# Power_1.net
KiCad netlist of a schematic drawn in Altium Designer
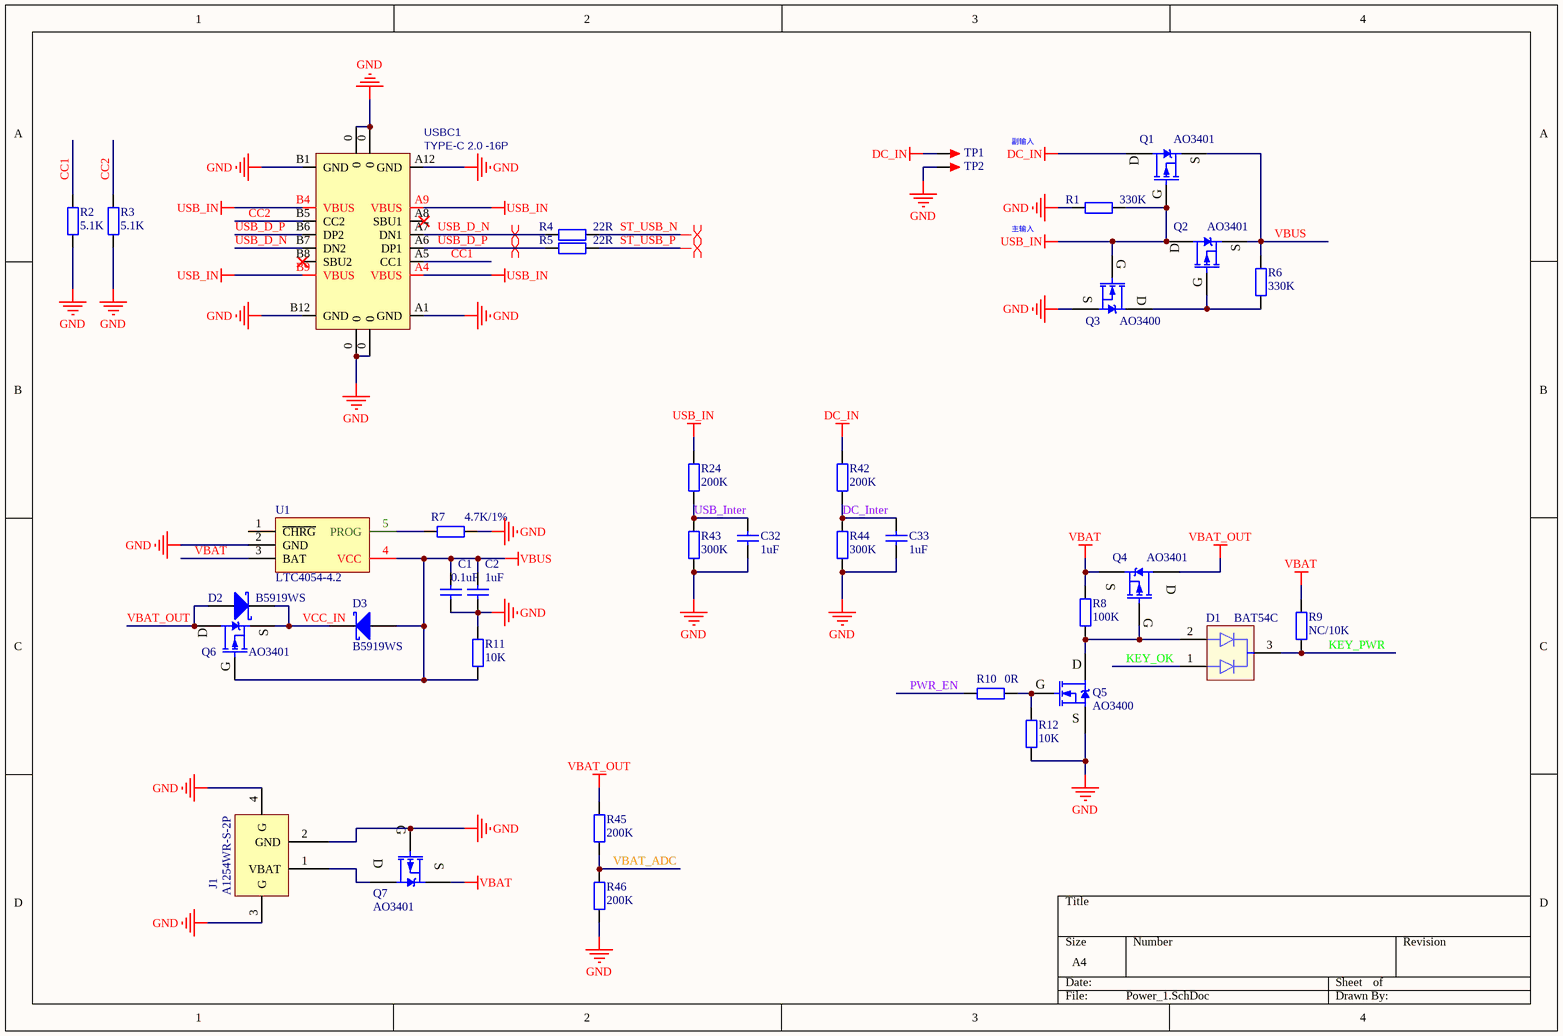
[diagram p0: Power_1.SchDoc]

(export (version "E")
  (design (tool "Eeschema 10.0.6"))
  (components
    (comp (ref "C1")
      (value "0.1uF")
      (footprint "C0402_L")
      (description "贴片电容")
      (libsource (lib "0.1 - 电阻-电容-电感-晶振-晶体-磁珠-电位器") (part "C"))
    )
    (comp (ref "C2")
      (value "1uF")
      (footprint "C0402_L")
      (description "贴片电容")
      (libsource (lib "0.1 - 电阻-电容-电感-晶振-晶体-磁珠-电位器") (part "C"))
    )
    (comp (ref "C32")
      (value "1uF")
      (footprint "C0402_L")
      (description "贴片电容")
      (libsource (lib "0.1 - 电阻-电容-电感-晶振-晶体-磁珠-电位器") (part "C"))
    )
    (comp (ref "C33")
      (value "1uF")
      (footprint "C0402_L")
      (description "贴片电容")
      (libsource (lib "0.1 - 电阻-电容-电感-晶振-晶体-磁珠-电位器") (part "C"))
    )
    (comp (ref "D1")
      (value "BAT54C")
      (footprint "SOT23-3L")
      (description "共阴肖特基二极管")
      (libsource (lib "USER_Lib") (part "BAT54C"))
    )
    (comp (ref "D2")
      (value "B5919WS")
      (footprint "SOD-123F")
      (description "肖特基二极管")
      (libsource (lib "0.2 - 二极管-TVS-ESD-整流桥") (part "1N5819"))
    )
    (comp (ref "D3")
      (value "B5919WS")
      (footprint "SOD-123F")
      (description "肖特基二极管")
      (libsource (lib "0.2 - 二极管-TVS-ESD-整流桥") (part "1N5819"))
    )
    (comp (ref "J1")
      (value "A1254WR-S-2P")
      (footprint "A1254WR-S-2P")
      (description "长江连接器-卧式-2P")
      (libsource (lib "USER_Lib") (part "A1254WR-S-2P"))
    )
    (comp (ref "Q1")
      (value "AO3401")
      (footprint "SOT23-3L")
      (description "P沟道 30V/4.2A")
      (libsource (lib "0.4 - 三极管-场效应管-可控硅") (part "AO3401"))
    )
    (comp (ref "Q2")
      (value "AO3401")
      (footprint "SOT23-3L")
      (description "P沟道 30V/4.2A")
      (libsource (lib "0.4 - 三极管-场效应管-可控硅") (part "AO3401"))
    )
    (comp (ref "Q3")
      (value "AO3400")
      (footprint "SOT23-3L")
      (description "N沟道 30V/4.2A")
      (libsource (lib "0.4 - 三极管-场效应管-可控硅") (part "AO3400"))
    )
    (comp (ref "Q4")
      (value "AO3401")
      (footprint "SOT23-3L")
      (description "P沟道 30V/4.2A")
      (libsource (lib "0.4 - 三极管-场效应管-可控硅") (part "AO3401"))
    )
    (comp (ref "Q5")
      (value "AO3400")
      (footprint "SOT23-3L")
      (description "N沟道 30V/4.2A")
      (libsource (lib "0.4 - 三极管-场效应管-可控硅") (part "AO3400"))
    )
    (comp (ref "Q6")
      (value "AO3401")
      (footprint "SOT23-3L")
      (description "P沟道 30V/4.2A")
      (libsource (lib "0.4 - 三极管-场效应管-可控硅") (part "AO3401"))
    )
    (comp (ref "Q7")
      (value "AO3401")
      (footprint "SOT23-3L")
      (description "P沟道 30V/4.2A")
      (libsource (lib "0.4 - 三极管-场效应管-可控硅") (part "AO3401"))
    )
    (comp (ref "R1")
      (value "330K")
      (footprint "R0402_L")
      (description "贴片电阻")
      (libsource (lib "0.1 - 电阻-电容-电感-晶振-晶体-磁珠-电位器") (part "R"))
    )
    (comp (ref "R2")
      (value "5.1K")
      (footprint "R0402_L")
      (description "贴片电阻")
      (libsource (lib "0.1 - 电阻-电容-电感-晶振-晶体-磁珠-电位器") (part "R"))
    )
    (comp (ref "R3")
      (value "5.1K")
      (footprint "R0402_L")
      (description "贴片电阻")
      (libsource (lib "0.1 - 电阻-电容-电感-晶振-晶体-磁珠-电位器") (part "R"))
    )
    (comp (ref "R4")
      (value "22R")
      (footprint "R0402_L")
      (description "贴片电阻")
      (libsource (lib "0.1 - 电阻-电容-电感-晶振-晶体-磁珠-电位器") (part "R"))
    )
    (comp (ref "R5")
      (value "22R")
      (footprint "R0402_L")
      (description "贴片电阻")
      (libsource (lib "0.1 - 电阻-电容-电感-晶振-晶体-磁珠-电位器") (part "R"))
    )
    (comp (ref "R6")
      (value "330K")
      (footprint "R0402_L")
      (description "贴片电阻")
      (libsource (lib "0.1 - 电阻-电容-电感-晶振-晶体-磁珠-电位器") (part "R"))
    )
    (comp (ref "R7")
      (value "4.7K/1%")
      (footprint "R0402_L")
      (description "贴片电阻")
      (libsource (lib "0.1 - 电阻-电容-电感-晶振-晶体-磁珠-电位器") (part "R"))
    )
    (comp (ref "R8")
      (value "100K")
      (footprint "R0402_L")
      (description "贴片电阻")
      (libsource (lib "0.1 - 电阻-电容-电感-晶振-晶体-磁珠-电位器") (part "R"))
    )
    (comp (ref "R9")
      (value "NC/10K")
      (footprint "R0402_L")
      (description "贴片电阻")
      (libsource (lib "0.1 - 电阻-电容-电感-晶振-晶体-磁珠-电位器") (part "R"))
    )
    (comp (ref "R10")
      (value "0R")
      (footprint "R0402_L")
      (description "贴片电阻")
      (libsource (lib "0.1 - 电阻-电容-电感-晶振-晶体-磁珠-电位器") (part "R"))
    )
    (comp (ref "R11")
      (value "10K")
      (footprint "R0402_L")
      (description "贴片电阻")
      (libsource (lib "0.1 - 电阻-电容-电感-晶振-晶体-磁珠-电位器") (part "R"))
    )
    (comp (ref "R12")
      (value "10K")
      (footprint "R0402_L")
      (description "贴片电阻")
      (libsource (lib "0.1 - 电阻-电容-电感-晶振-晶体-磁珠-电位器") (part "R"))
    )
    (comp (ref "R24")
      (value "200K")
      (footprint "R0402_L")
      (description "贴片电阻")
      (libsource (lib "0.1 - 电阻-电容-电感-晶振-晶体-磁珠-电位器") (part "R"))
    )
    (comp (ref "R42")
      (value "200K")
      (footprint "R0402_L")
      (description "贴片电阻")
      (libsource (lib "0.1 - 电阻-电容-电感-晶振-晶体-磁珠-电位器") (part "R"))
    )
    (comp (ref "R43")
      (value "300K")
      (footprint "R0402_L")
      (description "贴片电阻")
      (libsource (lib "0.1 - 电阻-电容-电感-晶振-晶体-磁珠-电位器") (part "R"))
    )
    (comp (ref "R44")
      (value "300K")
      (footprint "R0402_L")
      (description "贴片电阻")
      (libsource (lib "0.1 - 电阻-电容-电感-晶振-晶体-磁珠-电位器") (part "R"))
    )
    (comp (ref "R45")
      (value "200K")
      (footprint "R0402_L")
      (description "贴片电阻")
      (libsource (lib "0.1 - 电阻-电容-电感-晶振-晶体-磁珠-电位器") (part "R"))
    )
    (comp (ref "R46")
      (value "200K")
      (footprint "R0402_L")
      (description "贴片电阻")
      (libsource (lib "0.1 - 电阻-电容-电感-晶振-晶体-磁珠-电位器") (part "R"))
    )
    (comp (ref "TP1")
      (value "TEST")
      (footprint "TEST 1")
      (description "测试点")
      (libsource (lib "0.5 - 按键-开关-蜂鸣器-保险丝-电池-测试点-Mark点") (part "TEST"))
    )
    (comp (ref "TP2")
      (value "TEST")
      (footprint "TEST 1")
      (description "测试点")
      (libsource (lib "0.5 - 按键-开关-蜂鸣器-保险丝-电池-测试点-Mark点") (part "TEST"))
    )
    (comp (ref "U1")
      (value "LTC4054-4.2")
      (footprint "SOT23-5L")
      (description "锂电池充电IC")
      (libsource (lib "USER_Lib") (part "LTC4054-4.2"))
    )
    (comp (ref "USBC1")
      (value "TYPE-C 2.0 -16P")
      (footprint "USB-C-SMD_16P")
      (description "USB2.0_Type-C_16Pin母座")
      (libsource (lib "0.6 - 电源-以太网-音频-Type-C USB插座") (part "USB2.0_Type-C_16Pin"))
    )
  )
  (nets
    (net (code "1") (name "/CC1") (class "Default")
      (node (ref "R2") (pin "2") (pinfunction "2_2") (pintype "passive"))
      (node (ref "USBC1") (pin "A5") (pinfunction "CC1_A5") (pintype "passive"))
    )
    (net (code "2") (name "/CC2") (class "Default")
      (node (ref "R3") (pin "2") (pinfunction "2_2") (pintype "passive"))
      (node (ref "USBC1") (pin "B5") (pinfunction "CC2_B5") (pintype "passive"))
    )
    (net (code "3") (name "/DC_Inter") (class "Default")
      (node (ref "C33") (pin "2") (pinfunction "2_2") (pintype "passive"))
      (node (ref "R42") (pin "1") (pinfunction "1_1") (pintype "passive"))
      (node (ref "R44") (pin "2") (pinfunction "2_2") (pintype "passive"))
    )
    (net (code "4") (name "/KEY_OK") (class "Default")
      (node (ref "D1") (pin "1") (pinfunction "1_1") (pintype "passive"))
    )
    (net (code "5") (name "/KEY_PWR") (class "Default")
      (node (ref "D1") (pin "3") (pinfunction "3_3") (pintype "passive"))
      (node (ref "R9") (pin "1") (pinfunction "1_1") (pintype "passive"))
    )
    (net (code "6") (name "/PWR_EN") (class "Default")
      (node (ref "R10") (pin "2") (pinfunction "2_2") (pintype "passive"))
    )
    (net (code "7") (name "/ST_USB_N") (class "Default")
      (node (ref "R4") (pin "2") (pinfunction "2_2") (pintype "passive"))
    )
    (net (code "8") (name "/ST_USB_P") (class "Default")
      (node (ref "R5") (pin "2") (pinfunction "2_2") (pintype "passive"))
    )
    (net (code "9") (name "/USB_D_N") (class "Default")
      (node (ref "R4") (pin "1") (pinfunction "1_1") (pintype "passive"))
      (node (ref "USBC1") (pin "A7") (pinfunction "DN1_A7") (pintype "passive"))
      (node (ref "USBC1") (pin "B7") (pinfunction "DN2_B7") (pintype "passive"))
    )
    (net (code "10") (name "/USB_D_P") (class "Default")
      (node (ref "R5") (pin "1") (pinfunction "1_1") (pintype "passive"))
      (node (ref "USBC1") (pin "A6") (pinfunction "DP1_A6") (pintype "passive"))
      (node (ref "USBC1") (pin "B6") (pinfunction "DP2_B6") (pintype "passive"))
    )
    (net (code "11") (name "/USB_Inter") (class "Default")
      (node (ref "C32") (pin "2") (pinfunction "2_2") (pintype "passive"))
      (node (ref "R24") (pin "1") (pinfunction "1_1") (pintype "passive"))
      (node (ref "R43") (pin "2") (pinfunction "2_2") (pintype "passive"))
    )
    (net (code "12") (name "/VBAT_ADC") (class "Default")
      (node (ref "R45") (pin "1") (pinfunction "1_1") (pintype "passive"))
      (node (ref "R46") (pin "2") (pinfunction "2_2") (pintype "passive"))
    )
    (net (code "13") (name "/VCC_IN") (class "Default")
      (node (ref "D2") (pin "2") (pinfunction "K_2") (pintype "passive"))
      (node (ref "D3") (pin "2") (pinfunction "K_2") (pintype "passive"))
      (node (ref "Q6") (pin "2") (pinfunction "S_2") (pintype "passive"))
    )
    (net (code "14") (name "DC_IN") (class "Default")
      (node (ref "Q1") (pin "3") (pinfunction "D_3") (pintype "passive"))
      (node (ref "R42") (pin "2") (pinfunction "2_2") (pintype "passive"))
      (node (ref "TP1") (pin "1") (pinfunction "1_1") (pintype "passive"))
    )
    (net (code "15") (name "GND") (class "Default")
      (node (ref "C1") (pin "2") (pinfunction "2_2") (pintype "passive"))
      (node (ref "C2") (pin "2") (pinfunction "2_2") (pintype "passive"))
      (node (ref "C32") (pin "1") (pinfunction "1_1") (pintype "passive"))
      (node (ref "C33") (pin "1") (pinfunction "1_1") (pintype "passive"))
      (node (ref "J1") (pin "2") (pinfunction "GND_2") (pintype "passive"))
      (node (ref "J1") (pin "3") (pinfunction "G_3") (pintype "passive"))
      (node (ref "J1") (pin "4") (pinfunction "G_4") (pintype "passive"))
      (node (ref "Q3") (pin "2") (pinfunction "S_2") (pintype "passive"))
      (node (ref "Q5") (pin "2") (pinfunction "S_2") (pintype "passive"))
      (node (ref "Q7") (pin "1") (pinfunction "G_1") (pintype "passive"))
      (node (ref "R1") (pin "1") (pinfunction "1_1") (pintype "passive"))
      (node (ref "R11") (pin "2") (pinfunction "2_2") (pintype "passive"))
      (node (ref "R12") (pin "2") (pinfunction "2_2") (pintype "passive"))
      (node (ref "R2") (pin "1") (pinfunction "1_1") (pintype "passive"))
      (node (ref "R3") (pin "1") (pinfunction "1_1") (pintype "passive"))
      (node (ref "R43") (pin "1") (pinfunction "1_1") (pintype "passive"))
      (node (ref "R44") (pin "1") (pinfunction "1_1") (pintype "passive"))
      (node (ref "R46") (pin "1") (pinfunction "1_1") (pintype "passive"))
      (node (ref "R7") (pin "2") (pinfunction "2_2") (pintype "passive"))
      (node (ref "TP2") (pin "1") (pinfunction "1_1") (pintype "passive"))
      (node (ref "U1") (pin "2") (pinfunction "GND_2") (pintype "passive"))
      (node (ref "USBC1") (pin "0") (pinfunction "0_0") (pintype "passive"))
      (node (ref "USBC1") (pin "A1") (pinfunction "GND_A1") (pintype "passive"))
      (node (ref "USBC1") (pin "A12") (pinfunction "GND_A12") (pintype "passive"))
      (node (ref "USBC1") (pin "B1") (pinfunction "GND_B1") (pintype "passive"))
      (node (ref "USBC1") (pin "B12") (pinfunction "GND_B12") (pintype "passive"))
    )
    (net (code "16") (name "Net-(J1-VBAT)") (class "Default")
      (node (ref "J1") (pin "1") (pinfunction "VBAT_1") (pintype "passive"))
      (node (ref "Q7") (pin "3") (pinfunction "D_3") (pintype "passive"))
    )
    (net (code "17") (name "Net-(Q2-G)") (class "Default")
      (node (ref "Q2") (pin "1") (pinfunction "G_1") (pintype "passive"))
      (node (ref "Q3") (pin "3") (pinfunction "D_3") (pintype "passive"))
      (node (ref "R6") (pin "1") (pinfunction "1_1") (pintype "passive"))
    )
    (net (code "18") (name "Net-(Q4-G)") (class "Default")
      (node (ref "D1") (pin "2") (pinfunction "2_2") (pintype "passive"))
      (node (ref "Q4") (pin "1") (pinfunction "G_1") (pintype "passive"))
      (node (ref "Q5") (pin "3") (pinfunction "D_3") (pintype "passive"))
      (node (ref "R8") (pin "1") (pinfunction "1_1") (pintype "passive"))
    )
    (net (code "19") (name "Net-(Q5-G)") (class "Default")
      (node (ref "Q5") (pin "1") (pinfunction "G_1") (pintype "passive"))
      (node (ref "R10") (pin "1") (pinfunction "1_1") (pintype "passive"))
      (node (ref "R12") (pin "1") (pinfunction "1_1") (pintype "passive"))
    )
    (net (code "20") (name "Net-(U1-PROG)") (class "Default")
      (node (ref "R7") (pin "1") (pinfunction "1_1") (pintype "passive"))
      (node (ref "U1") (pin "5") (pinfunction "PROG_5") (pintype "passive"))
    )
    (net (code "21") (name "USB_IN") (class "Default")
      (node (ref "Q1") (pin "1") (pinfunction "G_1") (pintype "passive"))
      (node (ref "Q2") (pin "3") (pinfunction "D_3") (pintype "passive"))
      (node (ref "Q3") (pin "1") (pinfunction "G_1") (pintype "passive"))
      (node (ref "R1") (pin "2") (pinfunction "2_2") (pintype "passive"))
      (node (ref "R24") (pin "2") (pinfunction "2_2") (pintype "passive"))
      (node (ref "USBC1") (pin "A4") (pinfunction "VBUS_A4") (pintype "passive"))
      (node (ref "USBC1") (pin "A9") (pinfunction "VBUS_A9") (pintype "passive"))
      (node (ref "USBC1") (pin "B4") (pinfunction "VBUS_B4") (pintype "passive"))
      (node (ref "USBC1") (pin "B9") (pinfunction "VBUS_B9") (pintype "passive"))
    )
    (net (code "22") (name "VBAT") (class "Default")
      (node (ref "Q4") (pin "2") (pinfunction "S_2") (pintype "passive"))
      (node (ref "Q7") (pin "2") (pinfunction "S_2") (pintype "passive"))
      (node (ref "R8") (pin "2") (pinfunction "2_2") (pintype "passive"))
      (node (ref "R9") (pin "2") (pinfunction "2_2") (pintype "passive"))
      (node (ref "U1") (pin "3") (pinfunction "BAT_3") (pintype "passive"))
    )
    (net (code "23") (name "VBAT_OUT") (class "Default")
      (node (ref "D2") (pin "1") (pinfunction "A_1") (pintype "passive"))
      (node (ref "Q4") (pin "3") (pinfunction "D_3") (pintype "passive"))
      (node (ref "Q6") (pin "3") (pinfunction "D_3") (pintype "passive"))
      (node (ref "R45") (pin "2") (pinfunction "2_2") (pintype "passive"))
    )
    (net (code "24") (name "VBUS") (class "Default")
      (node (ref "C1") (pin "1") (pinfunction "1_1") (pintype "passive"))
      (node (ref "C2") (pin "1") (pinfunction "1_1") (pintype "passive"))
      (node (ref "D3") (pin "1") (pinfunction "A_1") (pintype "passive"))
      (node (ref "Q1") (pin "2") (pinfunction "S_2") (pintype "passive"))
      (node (ref "Q2") (pin "2") (pinfunction "S_2") (pintype "passive"))
      (node (ref "Q6") (pin "1") (pinfunction "G_1") (pintype "passive"))
      (node (ref "R11") (pin "1") (pinfunction "1_1") (pintype "passive"))
      (node (ref "R6") (pin "2") (pinfunction "2_2") (pintype "passive"))
      (node (ref "U1") (pin "4") (pinfunction "VCC_4") (pintype "passive"))
    )
    (net (code "25") (name "unconnected-(U1-~{CHRG}-Pad1)") (class "Default")
      (node (ref "U1") (pin "1") (pinfunction "~{CHRG}_1") (pintype "passive"))
    )
    (net (code "26") (name "unconnected-(USBC1-SBU1-PadA8)") (class "Default")
      (node (ref "USBC1") (pin "A8") (pinfunction "SBU1_A8") (pintype "passive+no_connect"))
    )
    (net (code "27") (name "unconnected-(USBC1-SBU2-PadB8)") (class "Default")
      (node (ref "USBC1") (pin "B8") (pinfunction "SBU2_B8") (pintype "passive+no_connect"))
    )
  )
)
